# ScoreBoard-V2.net
KiCad netlist of a schematic drawn in EAGLE
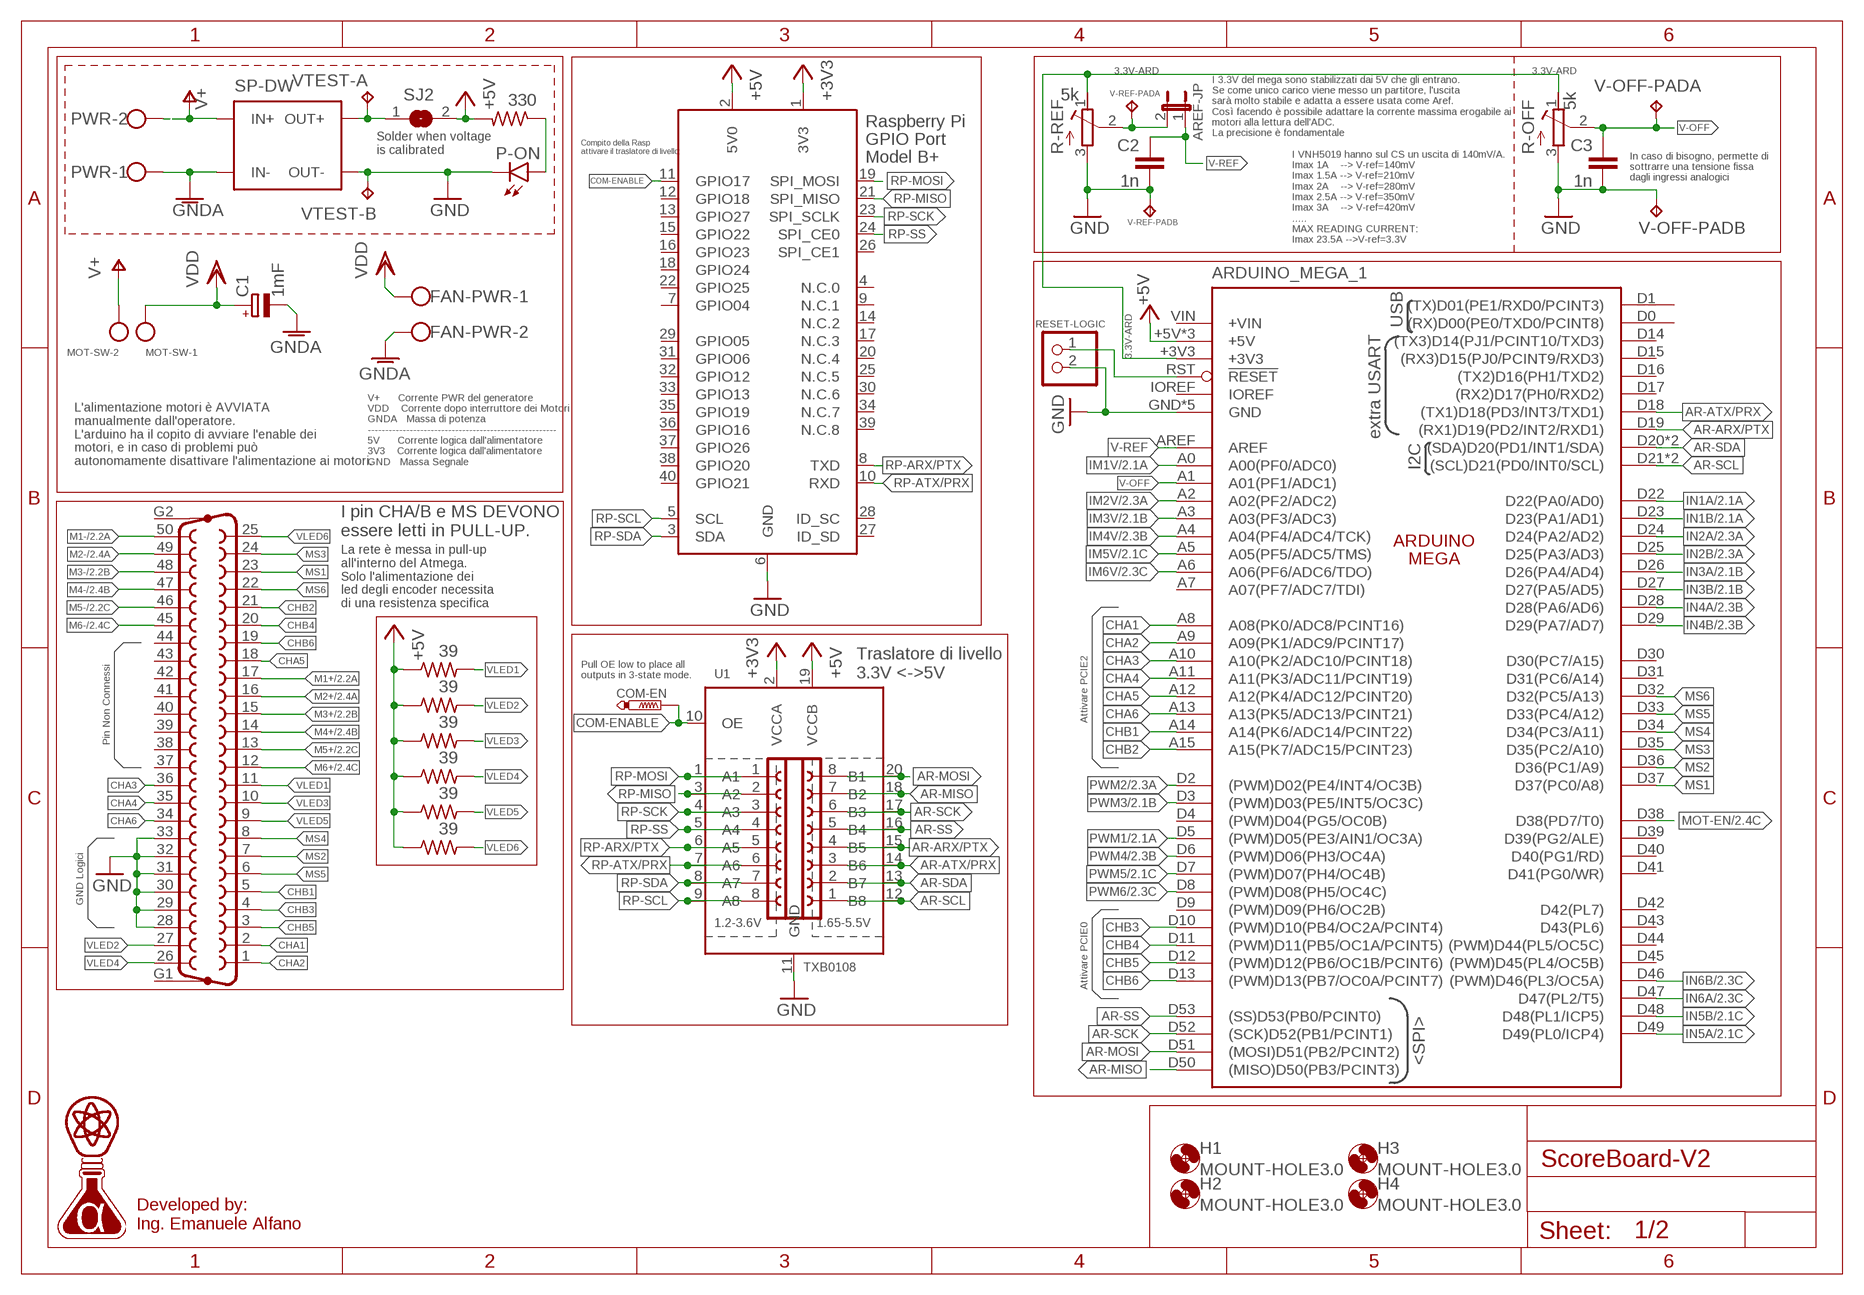
[diagram p0: schematic, sheet 1]
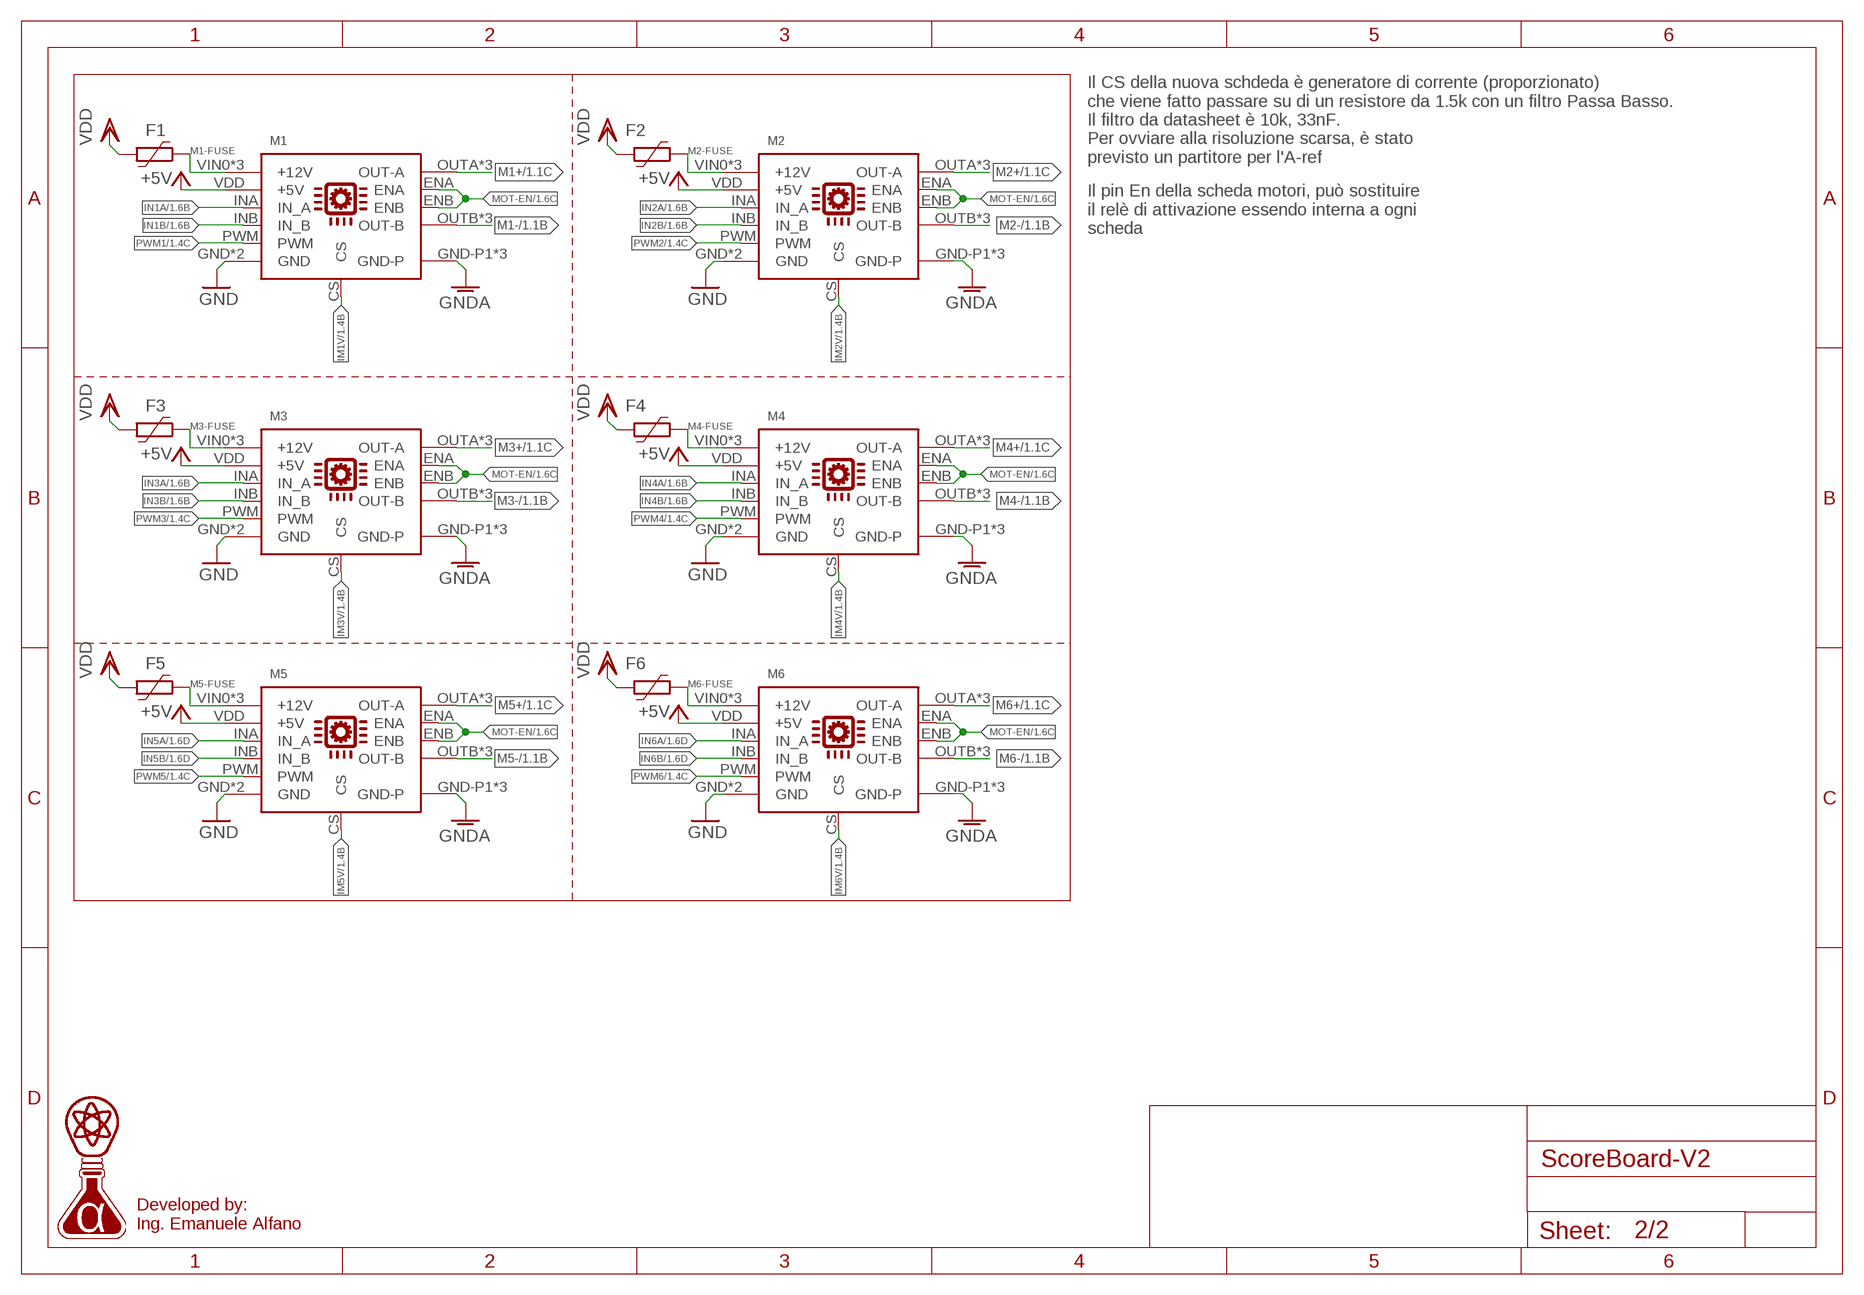
[diagram p1: schematic, sheet 2]

(export (version "E")
  (design (tool "Eeschema 10.0.6"))
  (components
    (comp (ref "F1")
      (value "2410-BOX")
      (footprint "eagle-import:BELFUSE0679-3000-12")
      (libsource (lib "eagle-import") (part "?2410-BOX"))
    )
    (comp (ref "F2")
      (value "2410-BOX")
      (footprint "eagle-import:BELFUSE0679-3000-12")
      (libsource (lib "eagle-import") (part "?2410-BOX"))
    )
    (comp (ref "F3")
      (value "2410-BOX")
      (footprint "eagle-import:BELFUSE0679-3000-12")
      (libsource (lib "eagle-import") (part "?2410-BOX"))
    )
    (comp (ref "F4")
      (value "2410-BOX")
      (footprint "eagle-import:BELFUSE0679-3000-12")
      (libsource (lib "eagle-import") (part "?2410-BOX"))
    )
    (comp (ref "F5")
      (value "2410-BOX")
      (footprint "eagle-import:BELFUSE0679-3000-12")
      (libsource (lib "eagle-import") (part "?2410-BOX"))
    )
    (comp (ref "F6")
      (value "2410-BOX")
      (footprint "eagle-import:BELFUSE0679-3000-12")
      (libsource (lib "eagle-import") (part "?2410-BOX"))
    )
    (comp (ref "M1")
      (value "VNH5019")
      (footprint "eagle-import:VNH5019")
      (libsource (lib "eagle-import") (part "VNH5019"))
    )
    (comp (ref "M2")
      (value "VNH5019")
      (footprint "eagle-import:VNH5019")
      (libsource (lib "eagle-import") (part "VNH5019"))
    )
    (comp (ref "M3")
      (value "VNH5019")
      (footprint "eagle-import:VNH5019")
      (libsource (lib "eagle-import") (part "VNH5019"))
    )
    (comp (ref "M4")
      (value "VNH5019")
      (footprint "eagle-import:VNH5019")
      (libsource (lib "eagle-import") (part "VNH5019"))
    )
    (comp (ref "M5")
      (value "VNH5019")
      (footprint "eagle-import:VNH5019")
      (libsource (lib "eagle-import") (part "VNH5019"))
    )
    (comp (ref "M6")
      (value "VNH5019")
      (footprint "eagle-import:VNH5019")
      (libsource (lib "eagle-import") (part "VNH5019"))
    )
    (comp (ref "ARDUINO_MEGA_1")
      (value "MEGA_ARDUINONO-HOLE")
      (footprint "eagle-import:MEGA-NO-HOLE")
      (libsource (lib "eagle-import") (part "MEGA_ARDUINONO-HOLE"))
    )
    (comp (ref "AREF-JP")
      (value "JP1E")
      (footprint "eagle-import:JP1")
      (libsource (lib "eagle-import") (part "JP1E"))
    )
    (comp (ref "C1")
      (value "1mF")
      (footprint "eagle-import:E5-13")
      (libsource (lib "eagle-import") (part "CPOL-EUE5-13"))
    )
    (comp (ref "C2")
      (value "1n")
      (footprint "eagle-import:C025-024X044")
      (libsource (lib "eagle-import") (part "C-EU025-024X044"))
    )
    (comp (ref "C3")
      (value "1n")
      (footprint "eagle-import:C025-024X044")
      (libsource (lib "eagle-import") (part "C-EU025-024X044"))
    )
    (comp (ref "COM-EN")
      (value "PTR1PAD1-13")
      (footprint "eagle-import:P1-13")
      (libsource (lib "eagle-import") (part "PTR1PAD1-13"))
    )
    (comp (ref "D-SUB50")
      (value "F50VP")
      (footprint "eagle-import:F50VP")
      (libsource (lib "eagle-import") (part "F50VP"))
    )
    (comp (ref "FAN-PWR")
      (value "W237-102")
      (footprint "eagle-import:W237-102")
      (fields (field (name "MPN") "237-102"))
      (libsource (lib "eagle-import") (part "W237-102"))
    )
    (comp (ref "H1")
      (value "MOUNT-HOLE3.0")
      (footprint "eagle-import:3,0")
      (libsource (lib "eagle-import") (part "MOUNT-HOLE3.0"))
    )
    (comp (ref "H2")
      (value "MOUNT-HOLE3.0")
      (footprint "eagle-import:3,0")
      (libsource (lib "eagle-import") (part "MOUNT-HOLE3.0"))
    )
    (comp (ref "H3")
      (value "MOUNT-HOLE3.0")
      (footprint "eagle-import:3,0")
      (libsource (lib "eagle-import") (part "MOUNT-HOLE3.0"))
    )
    (comp (ref "H4")
      (value "MOUNT-HOLE3.0")
      (footprint "eagle-import:3,0")
      (libsource (lib "eagle-import") (part "MOUNT-HOLE3.0"))
    )
    (comp (ref "MOT-SW")
      (value "W237-102")
      (footprint "eagle-import:W237-102")
      (fields (field (name "MPN") "237-102"))
      (libsource (lib "eagle-import") (part "W237-102"))
    )
    (comp (ref "P-ON")
      (value "LED3MM")
      (footprint "eagle-import:LED3MM")
      (libsource (lib "eagle-import") (part "LED3MM"))
    )
    (comp (ref "PWR")
      (value "W237-102")
      (footprint "eagle-import:W237-102")
      (fields (field (name "MPN") "237-102"))
      (libsource (lib "eagle-import") (part "W237-102"))
    )
    (comp (ref "R-OFF")
      (value "5k")
      (footprint "eagle-import:RTRIMT93YA")
      (libsource (lib "eagle-import") (part "R-TRIMMT93YA"))
    )
    (comp (ref "R-REF")
      (value "5k")
      (footprint "eagle-import:RTRIMT93YA")
      (libsource (lib "eagle-import") (part "R-TRIMMT93YA"))
    )
    (comp (ref "R1")
      (value "39")
      (footprint "eagle-import:0204_5")
      (libsource (lib "eagle-import") (part "R-US_0204/5"))
    )
    (comp (ref "R2")
      (value "39")
      (footprint "eagle-import:0204_5")
      (libsource (lib "eagle-import") (part "R-US_0204/5"))
    )
    (comp (ref "R3")
      (value "39")
      (footprint "eagle-import:0204_5")
      (libsource (lib "eagle-import") (part "R-US_0204/5"))
    )
    (comp (ref "R4")
      (value "39")
      (footprint "eagle-import:0204_5")
      (libsource (lib "eagle-import") (part "R-US_0204/5"))
    )
    (comp (ref "R5")
      (value "39")
      (footprint "eagle-import:0204_5")
      (libsource (lib "eagle-import") (part "R-US_0204/5"))
    )
    (comp (ref "R6")
      (value "39")
      (footprint "eagle-import:0204_5")
      (libsource (lib "eagle-import") (part "R-US_0204/5"))
    )
    (comp (ref "RASPBERRY-PY")
      (value "RASPI_GPIO_B+_BOX")
      (footprint "eagle-import:RASPI_GPIO_B+_BOX")
      (libsource (lib "eagle-import") (part "RASPI_GPIO_B+_BOX"))
    )
    (comp (ref "RESET-LOGIC")
      (value "PINHD-1X2")
      (footprint "eagle-import:1X02")
      (libsource (lib "eagle-import") (part "PINHD-1X2"))
    )
    (comp (ref "RL")
      (value "330")
      (footprint "eagle-import:0204_7")
      (libsource (lib "eagle-import") (part "R-US_0204/7"))
    )
    (comp (ref "SJ2")
      (value "SJ")
      (footprint "eagle-import:SJ")
      (fields (field (name "SPICEPREFIX") "B"))
      (libsource (lib "eagle-import") (part "SJ"))
    )
    (comp (ref "SP-DW")
      (value "DC/DC-STEP-DOWNGLOB")
      (footprint "eagle-import:DC_DC-STEP-DOWN-UNIVERSAL")
      (libsource (lib "eagle-import") (part "DC/DC-STEP-DOWNGLOB"))
    )
    (comp (ref "SV1")
      (value "FE08-1")
      (footprint "eagle-import:FE08")
      (libsource (lib "eagle-import") (part "FE08-1"))
    )
    (comp (ref "SV2")
      (value "FE08-1")
      (footprint "eagle-import:FE08")
      (libsource (lib "eagle-import") (part "FE08-1"))
    )
    (comp (ref "U1")
      (value "TXB0108")
      (footprint "eagle-import:TSSOP20")
      (fields (field (name "MF") "Texas Instruments") (field (name "MP") "TXB0108PWR"))
      (libsource (lib "eagle-import") (part "TXB0108PWR"))
    )
    (comp (ref "V-OFF-PAD")
      (value "TP2P2-38-17")
      (footprint "eagle-import:P2-38-17")
      (fields (field (name "SPICEPREFIX") "X"))
      (libsource (lib "eagle-import") (part "TP2P2-38-17"))
    )
    (comp (ref "V-REF-PAD")
      (value "TP2P2-38-17")
      (footprint "eagle-import:P2-38-17")
      (fields (field (name "SPICEPREFIX") "X"))
      (libsource (lib "eagle-import") (part "TP2P2-38-17"))
    )
    (comp (ref "VTEST-")
      (value "TP2P2-38-17")
      (footprint "eagle-import:P2-38-17")
      (fields (field (name "SPICEPREFIX") "X"))
      (libsource (lib "eagle-import") (part "TP2P2-38-17"))
    )
  )
  (nets
    (net (code "1") (name "+3V3") (class "Default")
      (node (ref "RASPBERRY-PY") (pin "1") (pinfunction "3V3_1") (pintype "power_in"))
      (node (ref "U1") (pin "2") (pinfunction "VCCA_2") (pintype "bidirectional"))
    )
    (net (code "2") (name "+5V") (class "Default")
      (node (ref "ARDUINO_MEGA_1") (pin "+5V") (pinfunction "+5V_+5V") (pintype "bidirectional"))
      (node (ref "ARDUINO_MEGA_1") (pin "+5V1") (pinfunction "+5V_+5V1") (pintype "bidirectional"))
      (node (ref "ARDUINO_MEGA_1") (pin "+5V2") (pinfunction "+5V_+5V2") (pintype "bidirectional"))
      (node (ref "M1") (pin "VDD") (pinfunction "+5V_VDD") (pintype "bidirectional"))
      (node (ref "M2") (pin "VDD") (pinfunction "+5V_VDD") (pintype "bidirectional"))
      (node (ref "M3") (pin "VDD") (pinfunction "+5V_VDD") (pintype "bidirectional"))
      (node (ref "M4") (pin "VDD") (pinfunction "+5V_VDD") (pintype "bidirectional"))
      (node (ref "M5") (pin "VDD") (pinfunction "+5V_VDD") (pintype "bidirectional"))
      (node (ref "M6") (pin "VDD") (pinfunction "+5V_VDD") (pintype "bidirectional"))
      (node (ref "R1") (pin "1") (pinfunction "1_1") (pintype "passive"))
      (node (ref "R2") (pin "1") (pinfunction "1_1") (pintype "passive"))
      (node (ref "R3") (pin "1") (pinfunction "1_1") (pintype "passive"))
      (node (ref "R4") (pin "1") (pinfunction "1_1") (pintype "passive"))
      (node (ref "R5") (pin "1") (pinfunction "1_1") (pintype "passive"))
      (node (ref "R6") (pin "1") (pinfunction "1_1") (pintype "passive"))
      (node (ref "RASPBERRY-PY") (pin "2") (pinfunction "5V0_2") (pintype "power_in"))
      (node (ref "RL") (pin "2") (pinfunction "2_2") (pintype "passive"))
      (node (ref "SJ2") (pin "2") (pinfunction "2_2") (pintype "passive"))
      (node (ref "U1") (pin "19") (pinfunction "VCCB_19") (pintype "bidirectional"))
    )
    (net (code "3") (name "3.3V-ARD") (class "Default")
      (node (ref "ARDUINO_MEGA_1") (pin "+3V3") (pinfunction "+3V3_+3V3") (pintype "bidirectional"))
      (node (ref "R-OFF") (pin "1") (pinfunction "E_1") (pintype "passive"))
      (node (ref "R-REF") (pin "1") (pinfunction "E_1") (pintype "passive"))
    )
    (net (code "4") (name "AR-ARX{slash}PTX") (class "Default")
      (node (ref "ARDUINO_MEGA_1") (pin "D19") (pinfunction "(RX1)D19(PD2/INT2/RXD1)_D19") (pintype "bidirectional"))
      (node (ref "SV2") (pin "4") (pinfunction "4_4") (pintype "passive"))
      (node (ref "U1") (pin "15") (pinfunction "B5_15") (pintype "bidirectional"))
    )
    (net (code "5") (name "AR-ATX{slash}PRX") (class "Default")
      (node (ref "ARDUINO_MEGA_1") (pin "D18") (pinfunction "(TX1)D18(PD3/INT3/TXD1)_D18") (pintype "bidirectional"))
      (node (ref "SV2") (pin "3") (pinfunction "3_3") (pintype "passive"))
      (node (ref "U1") (pin "14") (pinfunction "B6_14") (pintype "bidirectional"))
    )
    (net (code "6") (name "AR-MISO") (class "Default")
      (node (ref "ARDUINO_MEGA_1") (pin "D50") (pinfunction "(MISO)D50(PB3/PCINT3)_D50") (pintype "bidirectional"))
      (node (ref "SV2") (pin "7") (pinfunction "7_7") (pintype "passive"))
      (node (ref "U1") (pin "18") (pinfunction "B2_18") (pintype "bidirectional"))
    )
    (net (code "7") (name "AR-MOSI") (class "Default")
      (node (ref "ARDUINO_MEGA_1") (pin "D51") (pinfunction "(MOSI)D51(PB2/PCINT2)_D51") (pintype "bidirectional"))
      (node (ref "SV2") (pin "8") (pinfunction "8_8") (pintype "passive"))
      (node (ref "U1") (pin "20") (pinfunction "B1_20") (pintype "bidirectional"))
    )
    (net (code "8") (name "AR-SCK") (class "Default")
      (node (ref "ARDUINO_MEGA_1") (pin "D52") (pinfunction "(SCK)D52(PB1/PCINT1)_D52") (pintype "bidirectional"))
      (node (ref "SV2") (pin "6") (pinfunction "6_6") (pintype "passive"))
      (node (ref "U1") (pin "17") (pinfunction "B3_17") (pintype "bidirectional"))
    )
    (net (code "9") (name "AR-SCL") (class "Default")
      (node (ref "ARDUINO_MEGA_1") (pin "D21") (pinfunction "(SCL)D21(PD0/INT0/SCL)_D21") (pintype "bidirectional"))
      (node (ref "ARDUINO_MEGA_1") (pin "SCL1") (pinfunction "(SCL)D21(PD0/INT0/SCL)_SCL1") (pintype "bidirectional"))
      (node (ref "SV2") (pin "1") (pinfunction "1_1") (pintype "passive"))
      (node (ref "U1") (pin "12") (pinfunction "B8_12") (pintype "bidirectional"))
    )
    (net (code "10") (name "AR-SDA") (class "Default")
      (node (ref "ARDUINO_MEGA_1") (pin "D20") (pinfunction "(SDA)D20(PD1/INT1/SDA)_D20") (pintype "bidirectional"))
      (node (ref "ARDUINO_MEGA_1") (pin "SDA1") (pinfunction "(SDA)D20(PD1/INT1/SDA)_SDA1") (pintype "bidirectional"))
      (node (ref "SV2") (pin "2") (pinfunction "2_2") (pintype "passive"))
      (node (ref "U1") (pin "13") (pinfunction "B7_13") (pintype "bidirectional"))
    )
    (net (code "11") (name "AR-SS") (class "Default")
      (node (ref "ARDUINO_MEGA_1") (pin "D53") (pinfunction "(SS)D53(PB0/PCINT0)_D53") (pintype "bidirectional"))
      (node (ref "SV2") (pin "5") (pinfunction "5_5") (pintype "passive"))
      (node (ref "U1") (pin "16") (pinfunction "B4_16") (pintype "bidirectional"))
    )
    (net (code "12") (name "CHA1") (class "Default")
      (node (ref "ARDUINO_MEGA_1") (pin "A8") (pinfunction "A08(PK0/ADC8/PCINT16)_A8") (pintype "bidirectional"))
      (node (ref "D-SUB50") (pin "2") (pinfunction "2_2") (pintype "passive"))
    )
    (net (code "13") (name "CHA2") (class "Default")
      (node (ref "ARDUINO_MEGA_1") (pin "A9") (pinfunction "A09(PK1/ADC9/PCINT17)_A9") (pintype "bidirectional"))
      (node (ref "D-SUB50") (pin "1") (pinfunction "1_1") (pintype "passive"))
    )
    (net (code "14") (name "CHA3") (class "Default")
      (node (ref "ARDUINO_MEGA_1") (pin "A10") (pinfunction "A10(PK2/ADC10/PCINT18)_A10") (pintype "bidirectional"))
      (node (ref "D-SUB50") (pin "36") (pinfunction "36_36") (pintype "passive"))
    )
    (net (code "15") (name "CHA4") (class "Default")
      (node (ref "ARDUINO_MEGA_1") (pin "A11") (pinfunction "A11(PK3/ADC11/PCINT19)_A11") (pintype "bidirectional"))
      (node (ref "D-SUB50") (pin "35") (pinfunction "35_35") (pintype "passive"))
    )
    (net (code "16") (name "CHA5") (class "Default")
      (node (ref "ARDUINO_MEGA_1") (pin "A12") (pinfunction "A12(PK4/ADC12/PCINT20)_A12") (pintype "bidirectional"))
      (node (ref "D-SUB50") (pin "18") (pinfunction "18_18") (pintype "passive"))
    )
    (net (code "17") (name "CHA6") (class "Default")
      (node (ref "ARDUINO_MEGA_1") (pin "A13") (pinfunction "A13(PK5/ADC13/PCINT21)_A13") (pintype "bidirectional"))
      (node (ref "D-SUB50") (pin "34") (pinfunction "34_34") (pintype "passive"))
    )
    (net (code "18") (name "CHB1") (class "Default")
      (node (ref "ARDUINO_MEGA_1") (pin "A14") (pinfunction "A14(PK6/ADC14/PCINT22)_A14") (pintype "bidirectional"))
      (node (ref "D-SUB50") (pin "5") (pinfunction "5_5") (pintype "passive"))
    )
    (net (code "19") (name "CHB2") (class "Default")
      (node (ref "ARDUINO_MEGA_1") (pin "A15") (pinfunction "A15(PK7/ADC15/PCINT23)_A15") (pintype "bidirectional"))
      (node (ref "D-SUB50") (pin "21") (pinfunction "21_21") (pintype "passive"))
    )
    (net (code "20") (name "CHB3") (class "Default")
      (node (ref "ARDUINO_MEGA_1") (pin "D10") (pinfunction "(PWM)D10(PB4/OC2A/PCINT4)_D10") (pintype "bidirectional"))
      (node (ref "D-SUB50") (pin "4") (pinfunction "4_4") (pintype "passive"))
    )
    (net (code "21") (name "CHB4") (class "Default")
      (node (ref "ARDUINO_MEGA_1") (pin "D11") (pinfunction "(PWM)D11(PB5/OC1A/PCINT5)_D11") (pintype "bidirectional"))
      (node (ref "D-SUB50") (pin "20") (pinfunction "20_20") (pintype "passive"))
    )
    (net (code "22") (name "CHB5") (class "Default")
      (node (ref "ARDUINO_MEGA_1") (pin "D12") (pinfunction "(PWM)D12(PB6/OC1B/PCINT6)_D12") (pintype "bidirectional"))
      (node (ref "D-SUB50") (pin "3") (pinfunction "3_3") (pintype "passive"))
    )
    (net (code "23") (name "CHB6") (class "Default")
      (node (ref "ARDUINO_MEGA_1") (pin "D13") (pinfunction "(PWM)D13(PB7/OC0A/PCINT7)_D13") (pintype "bidirectional"))
      (node (ref "D-SUB50") (pin "19") (pinfunction "19_19") (pintype "passive"))
    )
    (net (code "24") (name "COM-ENABLE") (class "Default")
      (node (ref "COM-EN") (pin "TP") (pinfunction "TP_TP") (pintype "input"))
      (node (ref "RASPBERRY-PY") (pin "11") (pinfunction "GPIO17_11") (pintype "bidirectional"))
      (node (ref "U1") (pin "10") (pinfunction "OE_10") (pintype "bidirectional"))
    )
    (net (code "25") (name "GND") (class "Default")
      (node (ref "ARDUINO_MEGA_1") (pin "GND") (pinfunction "GND_GND") (pintype "bidirectional"))
      (node (ref "ARDUINO_MEGA_1") (pin "GND1") (pinfunction "GND_GND1") (pintype "bidirectional"))
      (node (ref "ARDUINO_MEGA_1") (pin "GND2") (pinfunction "GND_GND2") (pintype "bidirectional"))
      (node (ref "ARDUINO_MEGA_1") (pin "GND3") (pinfunction "GND_GND3") (pintype "bidirectional"))
      (node (ref "ARDUINO_MEGA_1") (pin "GND4") (pinfunction "GND_GND4") (pintype "bidirectional"))
      (node (ref "C2") (pin "2") (pinfunction "2_2") (pintype "passive"))
      (node (ref "C3") (pin "2") (pinfunction "2_2") (pintype "passive"))
      (node (ref "D-SUB50") (pin "28") (pinfunction "28_28") (pintype "passive"))
      (node (ref "D-SUB50") (pin "29") (pinfunction "29_29") (pintype "passive"))
      (node (ref "D-SUB50") (pin "30") (pinfunction "30_30") (pintype "passive"))
      (node (ref "D-SUB50") (pin "31") (pinfunction "31_31") (pintype "passive"))
      (node (ref "D-SUB50") (pin "32") (pinfunction "32_32") (pintype "passive"))
      (node (ref "D-SUB50") (pin "33") (pinfunction "33_33") (pintype "passive"))
      (node (ref "M1") (pin "GND") (pinfunction "GND_GND") (pintype "bidirectional"))
      (node (ref "M1") (pin "GND1") (pinfunction "GND_GND1") (pintype "bidirectional"))
      (node (ref "M2") (pin "GND") (pinfunction "GND_GND") (pintype "bidirectional"))
      (node (ref "M2") (pin "GND1") (pinfunction "GND_GND1") (pintype "bidirectional"))
      (node (ref "M3") (pin "GND") (pinfunction "GND_GND") (pintype "bidirectional"))
      (node (ref "M3") (pin "GND1") (pinfunction "GND_GND1") (pintype "bidirectional"))
      (node (ref "M4") (pin "GND") (pinfunction "GND_GND") (pintype "bidirectional"))
      (node (ref "M4") (pin "GND1") (pinfunction "GND_GND1") (pintype "bidirectional"))
      (node (ref "M5") (pin "GND") (pinfunction "GND_GND") (pintype "bidirectional"))
      (node (ref "M5") (pin "GND1") (pinfunction "GND_GND1") (pintype "bidirectional"))
      (node (ref "M6") (pin "GND") (pinfunction "GND_GND") (pintype "bidirectional"))
      (node (ref "M6") (pin "GND1") (pinfunction "GND_GND1") (pintype "bidirectional"))
      (node (ref "P-ON") (pin "K") (pinfunction "C_K") (pintype "passive"))
      (node (ref "R-OFF") (pin "3") (pinfunction "A_3") (pintype "passive"))
      (node (ref "R-REF") (pin "3") (pinfunction "A_3") (pintype "passive"))
      (node (ref "RASPBERRY-PY") (pin "6") (pinfunction "GND_6") (pintype "power_in"))
      (node (ref "RESET-LOGIC") (pin "2") (pinfunction "2_2") (pintype "passive"))
      (node (ref "SP-DW") (pin "OUT-") (pinfunction "OUT-_OUT-") (pintype "bidirectional"))
      (node (ref "SP-DW") (pin "OUT-1") (pinfunction "OUT-_OUT-1") (pintype "bidirectional"))
      (node (ref "SP-DW") (pin "OUT-2") (pinfunction "OUT-_OUT-2") (pintype "bidirectional"))
      (node (ref "U1") (pin "11") (pinfunction "GND_11") (pintype "bidirectional"))
      (node (ref "V-OFF-PAD") (pin "TP-2") (pinfunction "TP_TP-2") (pintype "input"))
      (node (ref "V-REF-PAD") (pin "TP-2") (pinfunction "TP_TP-2") (pintype "input"))
      (node (ref "VTEST-") (pin "TP-2") (pinfunction "TP_TP-2") (pintype "input"))
    )
    (net (code "26") (name "GNDA") (class "Default")
      (node (ref "C1") (pin "-") (pinfunction "-_-") (pintype "passive"))
      (node (ref "FAN-PWR") (pin "2") (pinfunction "KL_2") (pintype "passive"))
      (node (ref "M1") (pin "GND-P1") (pinfunction "GND-P_GND-P1") (pintype "bidirectional"))
      (node (ref "M1") (pin "GND-P2") (pinfunction "GND-P_GND-P2") (pintype "bidirectional"))
      (node (ref "M1") (pin "GND-P3") (pinfunction "GND-P_GND-P3") (pintype "bidirectional"))
      (node (ref "M2") (pin "GND-P1") (pinfunction "GND-P_GND-P1") (pintype "bidirectional"))
      (node (ref "M2") (pin "GND-P2") (pinfunction "GND-P_GND-P2") (pintype "bidirectional"))
      (node (ref "M2") (pin "GND-P3") (pinfunction "GND-P_GND-P3") (pintype "bidirectional"))
      (node (ref "M3") (pin "GND-P1") (pinfunction "GND-P_GND-P1") (pintype "bidirectional"))
      (node (ref "M3") (pin "GND-P2") (pinfunction "GND-P_GND-P2") (pintype "bidirectional"))
      (node (ref "M3") (pin "GND-P3") (pinfunction "GND-P_GND-P3") (pintype "bidirectional"))
      (node (ref "M4") (pin "GND-P1") (pinfunction "GND-P_GND-P1") (pintype "bidirectional"))
      (node (ref "M4") (pin "GND-P2") (pinfunction "GND-P_GND-P2") (pintype "bidirectional"))
      (node (ref "M4") (pin "GND-P3") (pinfunction "GND-P_GND-P3") (pintype "bidirectional"))
      (node (ref "M5") (pin "GND-P1") (pinfunction "GND-P_GND-P1") (pintype "bidirectional"))
      (node (ref "M5") (pin "GND-P2") (pinfunction "GND-P_GND-P2") (pintype "bidirectional"))
      (node (ref "M5") (pin "GND-P3") (pinfunction "GND-P_GND-P3") (pintype "bidirectional"))
      (node (ref "M6") (pin "GND-P1") (pinfunction "GND-P_GND-P1") (pintype "bidirectional"))
      (node (ref "M6") (pin "GND-P2") (pinfunction "GND-P_GND-P2") (pintype "bidirectional"))
      (node (ref "M6") (pin "GND-P3") (pinfunction "GND-P_GND-P3") (pintype "bidirectional"))
      (node (ref "PWR") (pin "1") (pinfunction "KL_1") (pintype "passive"))
      (node (ref "SP-DW") (pin "IN-") (pinfunction "IN-_IN-") (pintype "bidirectional"))
      (node (ref "SP-DW") (pin "IN-1") (pinfunction "IN-_IN-1") (pintype "bidirectional"))
      (node (ref "SP-DW") (pin "IN-2") (pinfunction "IN-_IN-2") (pintype "bidirectional"))
    )
    (net (code "27") (name "IM1V") (class "Default")
      (node (ref "ARDUINO_MEGA_1") (pin "A0") (pinfunction "A00(PF0/ADC0)_A0") (pintype "bidirectional"))
      (node (ref "M1") (pin "CS") (pinfunction "CS_CS") (pintype "bidirectional"))
    )
    (net (code "28") (name "IM2V") (class "Default")
      (node (ref "ARDUINO_MEGA_1") (pin "A2") (pinfunction "A02(PF2/ADC2)_A2") (pintype "bidirectional"))
      (node (ref "M2") (pin "CS") (pinfunction "CS_CS") (pintype "bidirectional"))
    )
    (net (code "29") (name "IM3V") (class "Default")
      (node (ref "ARDUINO_MEGA_1") (pin "A3") (pinfunction "A03(PF3/ADC3)_A3") (pintype "bidirectional"))
      (node (ref "M3") (pin "CS") (pinfunction "CS_CS") (pintype "bidirectional"))
    )
    (net (code "30") (name "IM4V") (class "Default")
      (node (ref "ARDUINO_MEGA_1") (pin "A4") (pinfunction "A04(PF4/ADC4/TCK)_A4") (pintype "bidirectional"))
      (node (ref "M4") (pin "CS") (pinfunction "CS_CS") (pintype "bidirectional"))
    )
    (net (code "31") (name "IM5V") (class "Default")
      (node (ref "ARDUINO_MEGA_1") (pin "A5") (pinfunction "A05(PF5/ADC5/TMS)_A5") (pintype "bidirectional"))
      (node (ref "M5") (pin "CS") (pinfunction "CS_CS") (pintype "bidirectional"))
    )
    (net (code "32") (name "IM6V") (class "Default")
      (node (ref "ARDUINO_MEGA_1") (pin "A6") (pinfunction "A06(PF6/ADC6/TDO)_A6") (pintype "bidirectional"))
      (node (ref "M6") (pin "CS") (pinfunction "CS_CS") (pintype "bidirectional"))
    )
    (net (code "33") (name "IN1A") (class "Default")
      (node (ref "ARDUINO_MEGA_1") (pin "D22") (pinfunction "D22(PA0/AD0)_D22") (pintype "bidirectional"))
      (node (ref "M1") (pin "INA") (pinfunction "IN_A_INA") (pintype "bidirectional"))
    )
    (net (code "34") (name "IN1B") (class "Default")
      (node (ref "ARDUINO_MEGA_1") (pin "D23") (pinfunction "D23(PA1/AD1)_D23") (pintype "bidirectional"))
      (node (ref "M1") (pin "INB") (pinfunction "IN_B_INB") (pintype "bidirectional"))
    )
    (net (code "35") (name "IN2A") (class "Default")
      (node (ref "ARDUINO_MEGA_1") (pin "D24") (pinfunction "D24(PA2/AD2)_D24") (pintype "bidirectional"))
      (node (ref "M2") (pin "INA") (pinfunction "IN_A_INA") (pintype "bidirectional"))
    )
    (net (code "36") (name "IN2B") (class "Default")
      (node (ref "ARDUINO_MEGA_1") (pin "D25") (pinfunction "D25(PA3/AD3)_D25") (pintype "bidirectional"))
      (node (ref "M2") (pin "INB") (pinfunction "IN_B_INB") (pintype "bidirectional"))
    )
    (net (code "37") (name "IN3A") (class "Default")
      (node (ref "ARDUINO_MEGA_1") (pin "D26") (pinfunction "D26(PA4/AD4)_D26") (pintype "bidirectional"))
      (node (ref "M3") (pin "INA") (pinfunction "IN_A_INA") (pintype "bidirectional"))
    )
    (net (code "38") (name "IN3B") (class "Default")
      (node (ref "ARDUINO_MEGA_1") (pin "D27") (pinfunction "D27(PA5/AD5)_D27") (pintype "bidirectional"))
      (node (ref "M3") (pin "INB") (pinfunction "IN_B_INB") (pintype "bidirectional"))
    )
    (net (code "39") (name "IN4A") (class "Default")
      (node (ref "ARDUINO_MEGA_1") (pin "D28") (pinfunction "D28(PA6/AD6)_D28") (pintype "bidirectional"))
      (node (ref "M4") (pin "INA") (pinfunction "IN_A_INA") (pintype "bidirectional"))
    )
    (net (code "40") (name "IN4B") (class "Default")
      (node (ref "ARDUINO_MEGA_1") (pin "D29") (pinfunction "D29(PA7/AD7)_D29") (pintype "bidirectional"))
      (node (ref "M4") (pin "INB") (pinfunction "IN_B_INB") (pintype "bidirectional"))
    )
    (net (code "41") (name "IN5A") (class "Default")
      (node (ref "ARDUINO_MEGA_1") (pin "D49") (pinfunction "D49(PL0/ICP4)_D49") (pintype "bidirectional"))
      (node (ref "M5") (pin "INA") (pinfunction "IN_A_INA") (pintype "bidirectional"))
    )
    (net (code "42") (name "IN5B") (class "Default")
      (node (ref "ARDUINO_MEGA_1") (pin "D48") (pinfunction "D48(PL1/ICP5)_D48") (pintype "bidirectional"))
      (node (ref "M5") (pin "INB") (pinfunction "IN_B_INB") (pintype "bidirectional"))
    )
    (net (code "43") (name "IN6A") (class "Default")
      (node (ref "ARDUINO_MEGA_1") (pin "D47") (pinfunction "D47(PL2/T5)_D47") (pintype "bidirectional"))
      (node (ref "M6") (pin "INA") (pinfunction "IN_A_INA") (pintype "bidirectional"))
    )
    (net (code "44") (name "IN6B") (class "Default")
      (node (ref "ARDUINO_MEGA_1") (pin "D46") (pinfunction "(PWM)D46(PL3/OC5A)_D46") (pintype "bidirectional"))
      (node (ref "M6") (pin "INB") (pinfunction "IN_B_INB") (pintype "bidirectional"))
    )
    (net (code "45") (name "M1+") (class "Default")
      (node (ref "D-SUB50") (pin "17") (pinfunction "17_17") (pintype "passive"))
      (node (ref "M1") (pin "OUTA") (pinfunction "OUT-A_OUTA") (pintype "bidirectional"))
      (node (ref "M1") (pin "OUTA2") (pinfunction "OUT-A_OUTA2") (pintype "bidirectional"))
      (node (ref "M1") (pin "OUTA3") (pinfunction "OUT-A_OUTA3") (pintype "bidirectional"))
    )
    (net (code "46") (name "M1-") (class "Default")
      (node (ref "D-SUB50") (pin "50") (pinfunction "50_50") (pintype "passive"))
      (node (ref "M1") (pin "OUTB") (pinfunction "OUT-B_OUTB") (pintype "bidirectional"))
      (node (ref "M1") (pin "OUTB1") (pinfunction "OUT-B_OUTB1") (pintype "bidirectional"))
      (node (ref "M1") (pin "OUTB3") (pinfunction "OUT-B_OUTB3") (pintype "bidirectional"))
    )
    (net (code "47") (name "M1-FUSE") (class "Default")
      (node (ref "F1") (pin "1") (pinfunction "1_1") (pintype "passive"))
      (node (ref "M1") (pin "VIN0") (pinfunction "+12V_VIN0") (pintype "bidirectional"))
      (node (ref "M1") (pin "VIN1") (pinfunction "+12V_VIN1") (pintype "bidirectional"))
      (node (ref "M1") (pin "VIN2") (pinfunction "+12V_VIN2") (pintype "bidirectional"))
    )
    (net (code "48") (name "M2+") (class "Default")
      (node (ref "D-SUB50") (pin "16") (pinfunction "16_16") (pintype "passive"))
      (node (ref "M2") (pin "OUTA") (pinfunction "OUT-A_OUTA") (pintype "bidirectional"))
      (node (ref "M2") (pin "OUTA2") (pinfunction "OUT-A_OUTA2") (pintype "bidirectional"))
      (node (ref "M2") (pin "OUTA3") (pinfunction "OUT-A_OUTA3") (pintype "bidirectional"))
    )
    (net (code "49") (name "M2-") (class "Default")
      (node (ref "D-SUB50") (pin "49") (pinfunction "49_49") (pintype "passive"))
      (node (ref "M2") (pin "OUTB") (pinfunction "OUT-B_OUTB") (pintype "bidirectional"))
      (node (ref "M2") (pin "OUTB1") (pinfunction "OUT-B_OUTB1") (pintype "bidirectional"))
      (node (ref "M2") (pin "OUTB3") (pinfunction "OUT-B_OUTB3") (pintype "bidirectional"))
    )
    (net (code "50") (name "M2-FUSE") (class "Default")
      (node (ref "F2") (pin "1") (pinfunction "1_1") (pintype "passive"))
      (node (ref "M2") (pin "VIN0") (pinfunction "+12V_VIN0") (pintype "bidirectional"))
      (node (ref "M2") (pin "VIN1") (pinfunction "+12V_VIN1") (pintype "bidirectional"))
      (node (ref "M2") (pin "VIN2") (pinfunction "+12V_VIN2") (pintype "bidirectional"))
    )
    (net (code "51") (name "M3+") (class "Default")
      (node (ref "D-SUB50") (pin "15") (pinfunction "15_15") (pintype "passive"))
      (node (ref "M3") (pin "OUTA") (pinfunction "OUT-A_OUTA") (pintype "bidirectional"))
      (node (ref "M3") (pin "OUTA2") (pinfunction "OUT-A_OUTA2") (pintype "bidirectional"))
      (node (ref "M3") (pin "OUTA3") (pinfunction "OUT-A_OUTA3") (pintype "bidirectional"))
    )
    (net (code "52") (name "M3-") (class "Default")
      (node (ref "D-SUB50") (pin "48") (pinfunction "48_48") (pintype "passive"))
      (node (ref "M3") (pin "OUTB") (pinfunction "OUT-B_OUTB") (pintype "bidirectional"))
      (node (ref "M3") (pin "OUTB1") (pinfunction "OUT-B_OUTB1") (pintype "bidirectional"))
      (node (ref "M3") (pin "OUTB3") (pinfunction "OUT-B_OUTB3") (pintype "bidirectional"))
    )
    (net (code "53") (name "M3-FUSE") (class "Default")
      (node (ref "F3") (pin "1") (pinfunction "1_1") (pintype "passive"))
      (node (ref "M3") (pin "VIN0") (pinfunction "+12V_VIN0") (pintype "bidirectional"))
      (node (ref "M3") (pin "VIN1") (pinfunction "+12V_VIN1") (pintype "bidirectional"))
      (node (ref "M3") (pin "VIN2") (pinfunction "+12V_VIN2") (pintype "bidirectional"))
    )
    (net (code "54") (name "M4+") (class "Default")
      (node (ref "D-SUB50") (pin "14") (pinfunction "14_14") (pintype "passive"))
      (node (ref "M4") (pin "OUTA") (pinfunction "OUT-A_OUTA") (pintype "bidirectional"))
      (node (ref "M4") (pin "OUTA2") (pinfunction "OUT-A_OUTA2") (pintype "bidirectional"))
      (node (ref "M4") (pin "OUTA3") (pinfunction "OUT-A_OUTA3") (pintype "bidirectional"))
    )
    (net (code "55") (name "M4-") (class "Default")
      (node (ref "D-SUB50") (pin "47") (pinfunction "47_47") (pintype "passive"))
      (node (ref "M4") (pin "OUTB") (pinfunction "OUT-B_OUTB") (pintype "bidirectional"))
      (node (ref "M4") (pin "OUTB1") (pinfunction "OUT-B_OUTB1") (pintype "bidirectional"))
      (node (ref "M4") (pin "OUTB3") (pinfunction "OUT-B_OUTB3") (pintype "bidirectional"))
    )
    (net (code "56") (name "M4-FUSE") (class "Default")
      (node (ref "F4") (pin "1") (pinfunction "1_1") (pintype "passive"))
      (node (ref "M4") (pin "VIN0") (pinfunction "+12V_VIN0") (pintype "bidirectional"))
      (node (ref "M4") (pin "VIN1") (pinfunction "+12V_VIN1") (pintype "bidirectional"))
      (node (ref "M4") (pin "VIN2") (pinfunction "+12V_VIN2") (pintype "bidirectional"))
    )
    (net (code "57") (name "M5+") (class "Default")
      (node (ref "D-SUB50") (pin "13") (pinfunction "13_13") (pintype "passive"))
      (node (ref "M5") (pin "OUTA") (pinfunction "OUT-A_OUTA") (pintype "bidirectional"))
      (node (ref "M5") (pin "OUTA2") (pinfunction "OUT-A_OUTA2") (pintype "bidirectional"))
      (node (ref "M5") (pin "OUTA3") (pinfunction "OUT-A_OUTA3") (pintype "bidirectional"))
    )
    (net (code "58") (name "M5-") (class "Default")
      (node (ref "D-SUB50") (pin "46") (pinfunction "46_46") (pintype "passive"))
      (node (ref "M5") (pin "OUTB") (pinfunction "OUT-B_OUTB") (pintype "bidirectional"))
      (node (ref "M5") (pin "OUTB1") (pinfunction "OUT-B_OUTB1") (pintype "bidirectional"))
      (node (ref "M5") (pin "OUTB3") (pinfunction "OUT-B_OUTB3") (pintype "bidirectional"))
    )
    (net (code "59") (name "M5-FUSE") (class "Default")
      (node (ref "F5") (pin "1") (pinfunction "1_1") (pintype "passive"))
      (node (ref "M5") (pin "VIN0") (pinfunction "+12V_VIN0") (pintype "bidirectional"))
      (node (ref "M5") (pin "VIN1") (pinfunction "+12V_VIN1") (pintype "bidirectional"))
      (node (ref "M5") (pin "VIN2") (pinfunction "+12V_VIN2") (pintype "bidirectional"))
    )
    (net (code "60") (name "M6+") (class "Default")
      (node (ref "D-SUB50") (pin "12") (pinfunction "12_12") (pintype "passive"))
      (node (ref "M6") (pin "OUTA") (pinfunction "OUT-A_OUTA") (pintype "bidirectional"))
      (node (ref "M6") (pin "OUTA2") (pinfunction "OUT-A_OUTA2") (pintype "bidirectional"))
      (node (ref "M6") (pin "OUTA3") (pinfunction "OUT-A_OUTA3") (pintype "bidirectional"))
    )
    (net (code "61") (name "M6-") (class "Default")
      (node (ref "D-SUB50") (pin "45") (pinfunction "45_45") (pintype "passive"))
      (node (ref "M6") (pin "OUTB") (pinfunction "OUT-B_OUTB") (pintype "bidirectional"))
      (node (ref "M6") (pin "OUTB1") (pinfunction "OUT-B_OUTB1") (pintype "bidirectional"))
      (node (ref "M6") (pin "OUTB3") (pinfunction "OUT-B_OUTB3") (pintype "bidirectional"))
    )
    (net (code "62") (name "M6-FUSE") (class "Default")
      (node (ref "F6") (pin "1") (pinfunction "1_1") (pintype "passive"))
      (node (ref "M6") (pin "VIN0") (pinfunction "+12V_VIN0") (pintype "bidirectional"))
      (node (ref "M6") (pin "VIN1") (pinfunction "+12V_VIN1") (pintype "bidirectional"))
      (node (ref "M6") (pin "VIN2") (pinfunction "+12V_VIN2") (pintype "bidirectional"))
    )
    (net (code "63") (name "MOT-EN") (class "Default")
      (node (ref "ARDUINO_MEGA_1") (pin "D38") (pinfunction "D38(PD7/T0)_D38") (pintype "bidirectional"))
      (node (ref "M1") (pin "ENA") (pinfunction "ENA_ENA") (pintype "bidirectional"))
      (node (ref "M1") (pin "ENB") (pinfunction "ENB_ENB") (pintype "bidirectional"))
      (node (ref "M2") (pin "ENA") (pinfunction "ENA_ENA") (pintype "bidirectional"))
      (node (ref "M2") (pin "ENB") (pinfunction "ENB_ENB") (pintype "bidirectional"))
      (node (ref "M3") (pin "ENA") (pinfunction "ENA_ENA") (pintype "bidirectional"))
      (node (ref "M3") (pin "ENB") (pinfunction "ENB_ENB") (pintype "bidirectional"))
      (node (ref "M4") (pin "ENA") (pinfunction "ENA_ENA") (pintype "bidirectional"))
      (node (ref "M4") (pin "ENB") (pinfunction "ENB_ENB") (pintype "bidirectional"))
      (node (ref "M5") (pin "ENA") (pinfunction "ENA_ENA") (pintype "bidirectional"))
      (node (ref "M5") (pin "ENB") (pinfunction "ENB_ENB") (pintype "bidirectional"))
      (node (ref "M6") (pin "ENA") (pinfunction "ENA_ENA") (pintype "bidirectional"))
      (node (ref "M6") (pin "ENB") (pinfunction "ENB_ENB") (pintype "bidirectional"))
    )
    (net (code "64") (name "MS1") (class "Default")
      (node (ref "ARDUINO_MEGA_1") (pin "D37") (pinfunction "D37(PC0/A8)_D37") (pintype "bidirectional"))
      (node (ref "D-SUB50") (pin "23") (pinfunction "23_23") (pintype "passive"))
    )
    (net (code "65") (name "MS2") (class "Default")
      (node (ref "ARDUINO_MEGA_1") (pin "D36") (pinfunction "D36(PC1/A9)_D36") (pintype "bidirectional"))
      (node (ref "D-SUB50") (pin "7") (pinfunction "7_7") (pintype "passive"))
    )
    (net (code "66") (name "MS3") (class "Default")
      (node (ref "ARDUINO_MEGA_1") (pin "D35") (pinfunction "D35(PC2/A10)_D35") (pintype "bidirectional"))
      (node (ref "D-SUB50") (pin "24") (pinfunction "24_24") (pintype "passive"))
    )
    (net (code "67") (name "MS4") (class "Default")
      (node (ref "ARDUINO_MEGA_1") (pin "D34") (pinfunction "D34(PC3/A11)_D34") (pintype "bidirectional"))
      (node (ref "D-SUB50") (pin "8") (pinfunction "8_8") (pintype "passive"))
    )
    (net (code "68") (name "MS5") (class "Default")
      (node (ref "ARDUINO_MEGA_1") (pin "D33") (pinfunction "D33(PC4/A12)_D33") (pintype "bidirectional"))
      (node (ref "D-SUB50") (pin "6") (pinfunction "6_6") (pintype "passive"))
    )
    (net (code "69") (name "MS6") (class "Default")
      (node (ref "ARDUINO_MEGA_1") (pin "D32") (pinfunction "D32(PC5/A13)_D32") (pintype "bidirectional"))
      (node (ref "D-SUB50") (pin "22") (pinfunction "22_22") (pintype "passive"))
    )
    (net (code "70") (name "Net-(ARDUINO_MEGA_1-~{RESET})") (class "Default")
      (node (ref "ARDUINO_MEGA_1") (pin "RST") (pinfunction "~{RESET}_RST") (pintype "bidirectional"))
      (node (ref "RESET-LOGIC") (pin "1") (pinfunction "1_1") (pintype "passive"))
    )
    (net (code "71") (name "Net-(P-ON-PadA)") (class "Default")
      (node (ref "P-ON") (pin "A") (pinfunction "A_A") (pintype "passive"))
      (node (ref "RL") (pin "1") (pinfunction "1_1") (pintype "passive"))
    )
    (net (code "72") (name "Net-(R-REF-S)") (class "Default")
      (node (ref "AREF-JP") (pin "2") (pinfunction "2_2") (pintype "passive"))
      (node (ref "R-REF") (pin "2") (pinfunction "S_2") (pintype "passive"))
      (node (ref "V-REF-PAD") (pin "TP-1") (pinfunction "TP_TP-1") (pintype "input"))
    )
    (net (code "73") (name "Net-(VTEST-A-TP)") (class "Default")
      (node (ref "SJ2") (pin "1") (pinfunction "1_1") (pintype "passive"))
      (node (ref "SP-DW") (pin "OUT+") (pinfunction "OUT+_OUT+") (pintype "bidirectional"))
      (node (ref "SP-DW") (pin "OUT+1") (pinfunction "OUT+_OUT+1") (pintype "bidirectional"))
      (node (ref "SP-DW") (pin "OUT+2") (pinfunction "OUT+_OUT+2") (pintype "bidirectional"))
      (node (ref "VTEST-") (pin "TP-1") (pinfunction "TP_TP-1") (pintype "input"))
    )
    (net (code "74") (name "PWM1") (class "Default")
      (node (ref "ARDUINO_MEGA_1") (pin "D5") (pinfunction "(PWM)D05(PE3/AIN1/OC3A)_D5") (pintype "bidirectional"))
      (node (ref "M1") (pin "PWM") (pinfunction "PWM_PWM") (pintype "bidirectional"))
    )
    (net (code "75") (name "PWM2") (class "Default")
      (node (ref "ARDUINO_MEGA_1") (pin "D2") (pinfunction "(PWM)D02(PE4/INT4/OC3B)_D2") (pintype "bidirectional"))
      (node (ref "M2") (pin "PWM") (pinfunction "PWM_PWM") (pintype "bidirectional"))
    )
    (net (code "76") (name "PWM3") (class "Default")
      (node (ref "ARDUINO_MEGA_1") (pin "D3") (pinfunction "(PWM)D03(PE5/INT5/OC3C)_D3") (pintype "bidirectional"))
      (node (ref "M3") (pin "PWM") (pinfunction "PWM_PWM") (pintype "bidirectional"))
    )
    (net (code "77") (name "PWM4") (class "Default")
      (node (ref "ARDUINO_MEGA_1") (pin "D6") (pinfunction "(PWM)D06(PH3/OC4A)_D6") (pintype "bidirectional"))
      (node (ref "M4") (pin "PWM") (pinfunction "PWM_PWM") (pintype "bidirectional"))
    )
    (net (code "78") (name "PWM5") (class "Default")
      (node (ref "ARDUINO_MEGA_1") (pin "D7") (pinfunction "(PWM)D07(PH4/OC4B)_D7") (pintype "bidirectional"))
      (node (ref "M5") (pin "PWM") (pinfunction "PWM_PWM") (pintype "bidirectional"))
    )
    (net (code "79") (name "PWM6") (class "Default")
      (node (ref "ARDUINO_MEGA_1") (pin "D8") (pinfunction "(PWM)D08(PH5/OC4C)_D8") (pintype "bidirectional"))
      (node (ref "M6") (pin "PWM") (pinfunction "PWM_PWM") (pintype "bidirectional"))
    )
    (net (code "80") (name "RP-ARX{slash}PTX") (class "Default")
      (node (ref "RASPBERRY-PY") (pin "8") (pinfunction "TXD_8") (pintype "bidirectional"))
      (node (ref "SV1") (pin "5") (pinfunction "5_5") (pintype "passive"))
      (node (ref "U1") (pin "6") (pinfunction "A5_6") (pintype "bidirectional"))
    )
    (net (code "81") (name "RP-ATX{slash}PRX") (class "Default")
      (node (ref "RASPBERRY-PY") (pin "10") (pinfunction "RXD_10") (pintype "bidirectional"))
      (node (ref "SV1") (pin "6") (pinfunction "6_6") (pintype "passive"))
      (node (ref "U1") (pin "7") (pinfunction "A6_7") (pintype "bidirectional"))
    )
    (net (code "82") (name "RP-MISO") (class "Default")
      (node (ref "RASPBERRY-PY") (pin "21") (pinfunction "SPI_MISO_21") (pintype "bidirectional"))
      (node (ref "SV1") (pin "2") (pinfunction "2_2") (pintype "passive"))
      (node (ref "U1") (pin "3") (pinfunction "A2_3") (pintype "bidirectional"))
    )
    (net (code "83") (name "RP-MOSI") (class "Default")
      (node (ref "RASPBERRY-PY") (pin "19") (pinfunction "SPI_MOSI_19") (pintype "bidirectional"))
      (node (ref "SV1") (pin "1") (pinfunction "1_1") (pintype "passive"))
      (node (ref "U1") (pin "1") (pinfunction "A1_1") (pintype "bidirectional"))
    )
    (net (code "84") (name "RP-SCK") (class "Default")
      (node (ref "RASPBERRY-PY") (pin "23") (pinfunction "SPI_SCLK_23") (pintype "bidirectional"))
      (node (ref "SV1") (pin "3") (pinfunction "3_3") (pintype "passive"))
      (node (ref "U1") (pin "4") (pinfunction "A3_4") (pintype "bidirectional"))
    )
    (net (code "85") (name "RP-SCL") (class "Default")
      (node (ref "RASPBERRY-PY") (pin "5") (pinfunction "SCL_5") (pintype "bidirectional"))
      (node (ref "SV1") (pin "8") (pinfunction "8_8") (pintype "passive"))
      (node (ref "U1") (pin "9") (pinfunction "A8_9") (pintype "bidirectional"))
    )
    (net (code "86") (name "RP-SDA") (class "Default")
      (node (ref "RASPBERRY-PY") (pin "3") (pinfunction "SDA_3") (pintype "bidirectional"))
      (node (ref "SV1") (pin "7") (pinfunction "7_7") (pintype "passive"))
      (node (ref "U1") (pin "8") (pinfunction "A7_8") (pintype "bidirectional"))
    )
    (net (code "87") (name "RP-SS") (class "Default")
      (node (ref "RASPBERRY-PY") (pin "24") (pinfunction "SPI_CE0_24") (pintype "bidirectional"))
      (node (ref "SV1") (pin "4") (pinfunction "4_4") (pintype "passive"))
      (node (ref "U1") (pin "5") (pinfunction "A4_5") (pintype "bidirectional"))
    )
    (net (code "88") (name "V+") (class "Default")
      (node (ref "MOT-SW") (pin "2") (pinfunction "KL_2") (pintype "passive"))
      (node (ref "PWR") (pin "2") (pinfunction "KL_2") (pintype "passive"))
      (node (ref "SP-DW") (pin "IN+") (pinfunction "IN+_IN+") (pintype "bidirectional"))
      (node (ref "SP-DW") (pin "IN+1") (pinfunction "IN+_IN+1") (pintype "bidirectional"))
      (node (ref "SP-DW") (pin "IN+2") (pinfunction "IN+_IN+2") (pintype "bidirectional"))
    )
    (net (code "89") (name "V-OFF") (class "Default")
      (node (ref "ARDUINO_MEGA_1") (pin "A1") (pinfunction "A01(PF1/ADC1)_A1") (pintype "bidirectional"))
      (node (ref "C3") (pin "1") (pinfunction "1_1") (pintype "passive"))
      (node (ref "R-OFF") (pin "2") (pinfunction "S_2") (pintype "passive"))
      (node (ref "V-OFF-PAD") (pin "TP-1") (pinfunction "TP_TP-1") (pintype "input"))
    )
    (net (code "90") (name "V-REF") (class "Default")
      (node (ref "ARDUINO_MEGA_1") (pin "AREF") (pinfunction "AREF_AREF") (pintype "bidirectional"))
      (node (ref "AREF-JP") (pin "1") (pinfunction "1_1") (pintype "passive"))
      (node (ref "C2") (pin "1") (pinfunction "1_1") (pintype "passive"))
    )
    (net (code "91") (name "VDD") (class "Default")
      (node (ref "C1") (pin "+") (pinfunction "+_+") (pintype "passive"))
      (node (ref "F1") (pin "2") (pinfunction "2_2") (pintype "passive"))
      (node (ref "F2") (pin "2") (pinfunction "2_2") (pintype "passive"))
      (node (ref "F3") (pin "2") (pinfunction "2_2") (pintype "passive"))
      (node (ref "F4") (pin "2") (pinfunction "2_2") (pintype "passive"))
      (node (ref "F5") (pin "2") (pinfunction "2_2") (pintype "passive"))
      (node (ref "F6") (pin "2") (pinfunction "2_2") (pintype "passive"))
      (node (ref "FAN-PWR") (pin "1") (pinfunction "KL_1") (pintype "passive"))
      (node (ref "MOT-SW") (pin "1") (pinfunction "KL_1") (pintype "passive"))
    )
    (net (code "92") (name "VLED1") (class "Default")
      (node (ref "D-SUB50") (pin "11") (pinfunction "11_11") (pintype "passive"))
      (node (ref "R1") (pin "2") (pinfunction "2_2") (pintype "passive"))
    )
    (net (code "93") (name "VLED2") (class "Default")
      (node (ref "D-SUB50") (pin "27") (pinfunction "27_27") (pintype "passive"))
      (node (ref "R2") (pin "2") (pinfunction "2_2") (pintype "passive"))
    )
    (net (code "94") (name "VLED3") (class "Default")
      (node (ref "D-SUB50") (pin "10") (pinfunction "10_10") (pintype "passive"))
      (node (ref "R3") (pin "2") (pinfunction "2_2") (pintype "passive"))
    )
    (net (code "95") (name "VLED4") (class "Default")
      (node (ref "D-SUB50") (pin "26") (pinfunction "26_26") (pintype "passive"))
      (node (ref "R4") (pin "2") (pinfunction "2_2") (pintype "passive"))
    )
    (net (code "96") (name "VLED5") (class "Default")
      (node (ref "D-SUB50") (pin "9") (pinfunction "9_9") (pintype "passive"))
      (node (ref "R5") (pin "2") (pinfunction "2_2") (pintype "passive"))
    )
    (net (code "97") (name "VLED6") (class "Default")
      (node (ref "D-SUB50") (pin "25") (pinfunction "25_25") (pintype "passive"))
      (node (ref "R6") (pin "2") (pinfunction "2_2") (pintype "passive"))
    )
    (net (code "98") (name "unconnected-(ARDUINO_MEGA_1-(PWM)D04(PG5{slash}OC0B)-PadD4)") (class "Default")
      (node (ref "ARDUINO_MEGA_1") (pin "D4") (pinfunction "(PWM)D04(PG5/OC0B)_D4") (pintype "bidirectional"))
    )
    (net (code "99") (name "unconnected-(ARDUINO_MEGA_1-(PWM)D09(PH6{slash}OC2B)-PadD9)") (class "Default")
      (node (ref "ARDUINO_MEGA_1") (pin "D9") (pinfunction "(PWM)D09(PH6/OC2B)_D9") (pintype "bidirectional"))
    )
    (net (code "100") (name "unconnected-(ARDUINO_MEGA_1-(PWM)D44(PL5{slash}OC5C)-PadD44)") (class "Default")
      (node (ref "ARDUINO_MEGA_1") (pin "D44") (pinfunction "(PWM)D44(PL5/OC5C)_D44") (pintype "bidirectional"))
    )
    (net (code "101") (name "unconnected-(ARDUINO_MEGA_1-(PWM)D45(PL4{slash}OC5B)-PadD45)") (class "Default")
      (node (ref "ARDUINO_MEGA_1") (pin "D45") (pinfunction "(PWM)D45(PL4/OC5B)_D45") (pintype "bidirectional"))
    )
    (net (code "102") (name "unconnected-(ARDUINO_MEGA_1-(RX)D00(PE0{slash}TXD0{slash}PCINT8)-PadD0)") (class "Default")
      (node (ref "ARDUINO_MEGA_1") (pin "D0") (pinfunction "(RX)D00(PE0/TXD0/PCINT8)_D0") (pintype "bidirectional"))
    )
    (net (code "103") (name "unconnected-(ARDUINO_MEGA_1-(RX2)D17(PH0{slash}RXD2)-PadD17)") (class "Default")
      (node (ref "ARDUINO_MEGA_1") (pin "D17") (pinfunction "(RX2)D17(PH0/RXD2)_D17") (pintype "bidirectional"))
    )
    (net (code "104") (name "unconnected-(ARDUINO_MEGA_1-(RX3)D15(PJ0{slash}PCINT9{slash}RXD3)-PadD15)") (class "Default")
      (node (ref "ARDUINO_MEGA_1") (pin "D15") (pinfunction "(RX3)D15(PJ0/PCINT9/RXD3)_D15") (pintype "bidirectional"))
    )
    (net (code "105") (name "unconnected-(ARDUINO_MEGA_1-(TX)D01(PE1{slash}RXD0{slash}PCINT3)-PadD1)") (class "Default")
      (node (ref "ARDUINO_MEGA_1") (pin "D1") (pinfunction "(TX)D01(PE1/RXD0/PCINT3)_D1") (pintype "bidirectional"))
    )
    (net (code "106") (name "unconnected-(ARDUINO_MEGA_1-(TX2)D16(PH1{slash}TXD2)-PadD16)") (class "Default")
      (node (ref "ARDUINO_MEGA_1") (pin "D16") (pinfunction "(TX2)D16(PH1/TXD2)_D16") (pintype "bidirectional"))
    )
    (net (code "107") (name "unconnected-(ARDUINO_MEGA_1-(TX3)D14(PJ1{slash}PCINT10{slash}TXD3)-PadD14)") (class "Default")
      (node (ref "ARDUINO_MEGA_1") (pin "D14") (pinfunction "(TX3)D14(PJ1/PCINT10/TXD3)_D14") (pintype "bidirectional"))
    )
    (net (code "108") (name "unconnected-(ARDUINO_MEGA_1-+VIN-PadVIN)") (class "Default")
      (node (ref "ARDUINO_MEGA_1") (pin "VIN") (pinfunction "+VIN_VIN") (pintype "bidirectional"))
    )
    (net (code "109") (name "unconnected-(ARDUINO_MEGA_1-A07(PF7{slash}ADC7{slash}TDI)-PadA7)") (class "Default")
      (node (ref "ARDUINO_MEGA_1") (pin "A7") (pinfunction "A07(PF7/ADC7/TDI)_A7") (pintype "bidirectional"))
    )
    (net (code "110") (name "unconnected-(ARDUINO_MEGA_1-D30(PC7{slash}A15)-PadD30)") (class "Default")
      (node (ref "ARDUINO_MEGA_1") (pin "D30") (pinfunction "D30(PC7/A15)_D30") (pintype "bidirectional"))
    )
    (net (code "111") (name "unconnected-(ARDUINO_MEGA_1-D31(PC6{slash}A14)-PadD31)") (class "Default")
      (node (ref "ARDUINO_MEGA_1") (pin "D31") (pinfunction "D31(PC6/A14)_D31") (pintype "bidirectional"))
    )
    (net (code "112") (name "unconnected-(ARDUINO_MEGA_1-D39(PG2{slash}ALE)-PadD39)") (class "Default")
      (node (ref "ARDUINO_MEGA_1") (pin "D39") (pinfunction "D39(PG2/ALE)_D39") (pintype "bidirectional"))
    )
    (net (code "113") (name "unconnected-(ARDUINO_MEGA_1-D40(PG1{slash}RD)-PadD40)") (class "Default")
      (node (ref "ARDUINO_MEGA_1") (pin "D40") (pinfunction "D40(PG1/RD)_D40") (pintype "bidirectional"))
    )
    (net (code "114") (name "unconnected-(ARDUINO_MEGA_1-D41(PG0{slash}WR)-PadD41)") (class "Default")
      (node (ref "ARDUINO_MEGA_1") (pin "D41") (pinfunction "D41(PG0/WR)_D41") (pintype "bidirectional"))
    )
    (net (code "115") (name "unconnected-(ARDUINO_MEGA_1-D42(PL7)-PadD42)") (class "Default")
      (node (ref "ARDUINO_MEGA_1") (pin "D42") (pinfunction "D42(PL7)_D42") (pintype "bidirectional"))
    )
    (net (code "116") (name "unconnected-(ARDUINO_MEGA_1-D43(PL6)-PadD43)") (class "Default")
      (node (ref "ARDUINO_MEGA_1") (pin "D43") (pinfunction "D43(PL6)_D43") (pintype "bidirectional"))
    )
    (net (code "117") (name "unconnected-(ARDUINO_MEGA_1-PadIOREF)") (class "Default")
      (node (ref "ARDUINO_MEGA_1") (pin "IOREF") (pinfunction "IOREF_IOREF") (pintype "bidirectional"))
    )
    (net (code "118") (name "unconnected-(D-SUB50-Pad37)") (class "Default")
      (node (ref "D-SUB50") (pin "37") (pinfunction "37_37") (pintype "passive"))
    )
    (net (code "119") (name "unconnected-(D-SUB50-Pad38)") (class "Default")
      (node (ref "D-SUB50") (pin "38") (pinfunction "38_38") (pintype "passive"))
    )
    (net (code "120") (name "unconnected-(D-SUB50-Pad39)") (class "Default")
      (node (ref "D-SUB50") (pin "39") (pinfunction "39_39") (pintype "passive"))
    )
    (net (code "121") (name "unconnected-(D-SUB50-Pad40)") (class "Default")
      (node (ref "D-SUB50") (pin "40") (pinfunction "40_40") (pintype "passive"))
    )
    (net (code "122") (name "unconnected-(D-SUB50-Pad41)") (class "Default")
      (node (ref "D-SUB50") (pin "41") (pinfunction "41_41") (pintype "passive"))
    )
    (net (code "123") (name "unconnected-(D-SUB50-Pad42)") (class "Default")
      (node (ref "D-SUB50") (pin "42") (pinfunction "42_42") (pintype "passive"))
    )
    (net (code "124") (name "unconnected-(D-SUB50-Pad43)") (class "Default")
      (node (ref "D-SUB50") (pin "43") (pinfunction "43_43") (pintype "passive"))
    )
    (net (code "125") (name "unconnected-(D-SUB50-Pad44)") (class "Default")
      (node (ref "D-SUB50") (pin "44") (pinfunction "44_44") (pintype "passive"))
    )
    (net (code "126") (name "unconnected-(D-SUB50-PadG1)") (class "Default")
      (node (ref "D-SUB50") (pin "G1") (pinfunction "G1_G1") (pintype "passive"))
    )
    (net (code "127") (name "unconnected-(D-SUB50-PadG2)") (class "Default")
      (node (ref "D-SUB50") (pin "G2") (pinfunction "G2_G2") (pintype "passive"))
    )
    (net (code "128") (name "unconnected-(RASPBERRY-PY-GPIO04-Pad7)") (class "Default")
      (node (ref "RASPBERRY-PY") (pin "7") (pinfunction "GPIO04_7") (pintype "bidirectional"))
    )
    (net (code "129") (name "unconnected-(RASPBERRY-PY-GPIO05-Pad29)") (class "Default")
      (node (ref "RASPBERRY-PY") (pin "29") (pinfunction "GPIO05_29") (pintype "no_connect"))
    )
    (net (code "130") (name "unconnected-(RASPBERRY-PY-GPIO06-Pad31)") (class "Default")
      (node (ref "RASPBERRY-PY") (pin "31") (pinfunction "GPIO06_31") (pintype "no_connect"))
    )
    (net (code "131") (name "unconnected-(RASPBERRY-PY-GPIO12-Pad32)") (class "Default")
      (node (ref "RASPBERRY-PY") (pin "32") (pinfunction "GPIO12_32") (pintype "no_connect"))
    )
    (net (code "132") (name "unconnected-(RASPBERRY-PY-GPIO13-Pad33)") (class "Default")
      (node (ref "RASPBERRY-PY") (pin "33") (pinfunction "GPIO13_33") (pintype "no_connect"))
    )
    (net (code "133") (name "unconnected-(RASPBERRY-PY-GPIO16-Pad36)") (class "Default")
      (node (ref "RASPBERRY-PY") (pin "36") (pinfunction "GPIO16_36") (pintype "no_connect"))
    )
    (net (code "134") (name "unconnected-(RASPBERRY-PY-GPIO18-Pad12)") (class "Default")
      (node (ref "RASPBERRY-PY") (pin "12") (pinfunction "GPIO18_12") (pintype "bidirectional"))
    )
    (net (code "135") (name "unconnected-(RASPBERRY-PY-GPIO19-Pad35)") (class "Default")
      (node (ref "RASPBERRY-PY") (pin "35") (pinfunction "GPIO19_35") (pintype "no_connect"))
    )
    (net (code "136") (name "unconnected-(RASPBERRY-PY-GPIO20-Pad38)") (class "Default")
      (node (ref "RASPBERRY-PY") (pin "38") (pinfunction "GPIO20_38") (pintype "no_connect"))
    )
    (net (code "137") (name "unconnected-(RASPBERRY-PY-GPIO21-Pad40)") (class "Default")
      (node (ref "RASPBERRY-PY") (pin "40") (pinfunction "GPIO21_40") (pintype "no_connect"))
    )
    (net (code "138") (name "unconnected-(RASPBERRY-PY-GPIO22-Pad15)") (class "Default")
      (node (ref "RASPBERRY-PY") (pin "15") (pinfunction "GPIO22_15") (pintype "bidirectional"))
    )
    (net (code "139") (name "unconnected-(RASPBERRY-PY-GPIO23-Pad16)") (class "Default")
      (node (ref "RASPBERRY-PY") (pin "16") (pinfunction "GPIO23_16") (pintype "bidirectional"))
    )
    (net (code "140") (name "unconnected-(RASPBERRY-PY-GPIO24-Pad18)") (class "Default")
      (node (ref "RASPBERRY-PY") (pin "18") (pinfunction "GPIO24_18") (pintype "bidirectional"))
    )
    (net (code "141") (name "unconnected-(RASPBERRY-PY-GPIO25-Pad22)") (class "Default")
      (node (ref "RASPBERRY-PY") (pin "22") (pinfunction "GPIO25_22") (pintype "bidirectional"))
    )
    (net (code "142") (name "unconnected-(RASPBERRY-PY-GPIO26-Pad37)") (class "Default")
      (node (ref "RASPBERRY-PY") (pin "37") (pinfunction "GPIO26_37") (pintype "no_connect"))
    )
    (net (code "143") (name "unconnected-(RASPBERRY-PY-GPIO27-Pad13)") (class "Default")
      (node (ref "RASPBERRY-PY") (pin "13") (pinfunction "GPIO27_13") (pintype "bidirectional"))
    )
    (net (code "144") (name "unconnected-(RASPBERRY-PY-ID_SC-Pad28)") (class "Default")
      (node (ref "RASPBERRY-PY") (pin "28") (pinfunction "ID_SC_28") (pintype "no_connect"))
    )
    (net (code "145") (name "unconnected-(RASPBERRY-PY-ID_SD-Pad27)") (class "Default")
      (node (ref "RASPBERRY-PY") (pin "27") (pinfunction "ID_SD_27") (pintype "no_connect"))
    )
    (net (code "146") (name "unconnected-(RASPBERRY-PY-N.C.0-Pad4)") (class "Default")
      (node (ref "RASPBERRY-PY") (pin "4") (pinfunction "N.C.0_4") (pintype "no_connect"))
    )
    (net (code "147") (name "unconnected-(RASPBERRY-PY-N.C.1-Pad9)") (class "Default")
      (node (ref "RASPBERRY-PY") (pin "9") (pinfunction "N.C.1_9") (pintype "no_connect"))
    )
    (net (code "148") (name "unconnected-(RASPBERRY-PY-N.C.2-Pad14)") (class "Default")
      (node (ref "RASPBERRY-PY") (pin "14") (pinfunction "N.C.2_14") (pintype "no_connect"))
    )
    (net (code "149") (name "unconnected-(RASPBERRY-PY-N.C.3-Pad17)") (class "Default")
      (node (ref "RASPBERRY-PY") (pin "17") (pinfunction "N.C.3_17") (pintype "no_connect"))
    )
    (net (code "150") (name "unconnected-(RASPBERRY-PY-N.C.4-Pad20)") (class "Default")
      (node (ref "RASPBERRY-PY") (pin "20") (pinfunction "N.C.4_20") (pintype "no_connect"))
    )
    (net (code "151") (name "unconnected-(RASPBERRY-PY-N.C.5-Pad25)") (class "Default")
      (node (ref "RASPBERRY-PY") (pin "25") (pinfunction "N.C.5_25") (pintype "no_connect"))
    )
    (net (code "152") (name "unconnected-(RASPBERRY-PY-N.C.6-Pad30)") (class "Default")
      (node (ref "RASPBERRY-PY") (pin "30") (pinfunction "N.C.6_30") (pintype "no_connect"))
    )
    (net (code "153") (name "unconnected-(RASPBERRY-PY-N.C.7-Pad34)") (class "Default")
      (node (ref "RASPBERRY-PY") (pin "34") (pinfunction "N.C.7_34") (pintype "no_connect"))
    )
    (net (code "154") (name "unconnected-(RASPBERRY-PY-N.C.8-Pad39)") (class "Default")
      (node (ref "RASPBERRY-PY") (pin "39") (pinfunction "N.C.8_39") (pintype "no_connect"))
    )
    (net (code "155") (name "unconnected-(RASPBERRY-PY-SPI_CE1-Pad26)") (class "Default")
      (node (ref "RASPBERRY-PY") (pin "26") (pinfunction "SPI_CE1_26") (pintype "bidirectional"))
    )
  )
)
